# mainboard-raspi.net
KiCad netlist of a schematic drawn in EAGLE
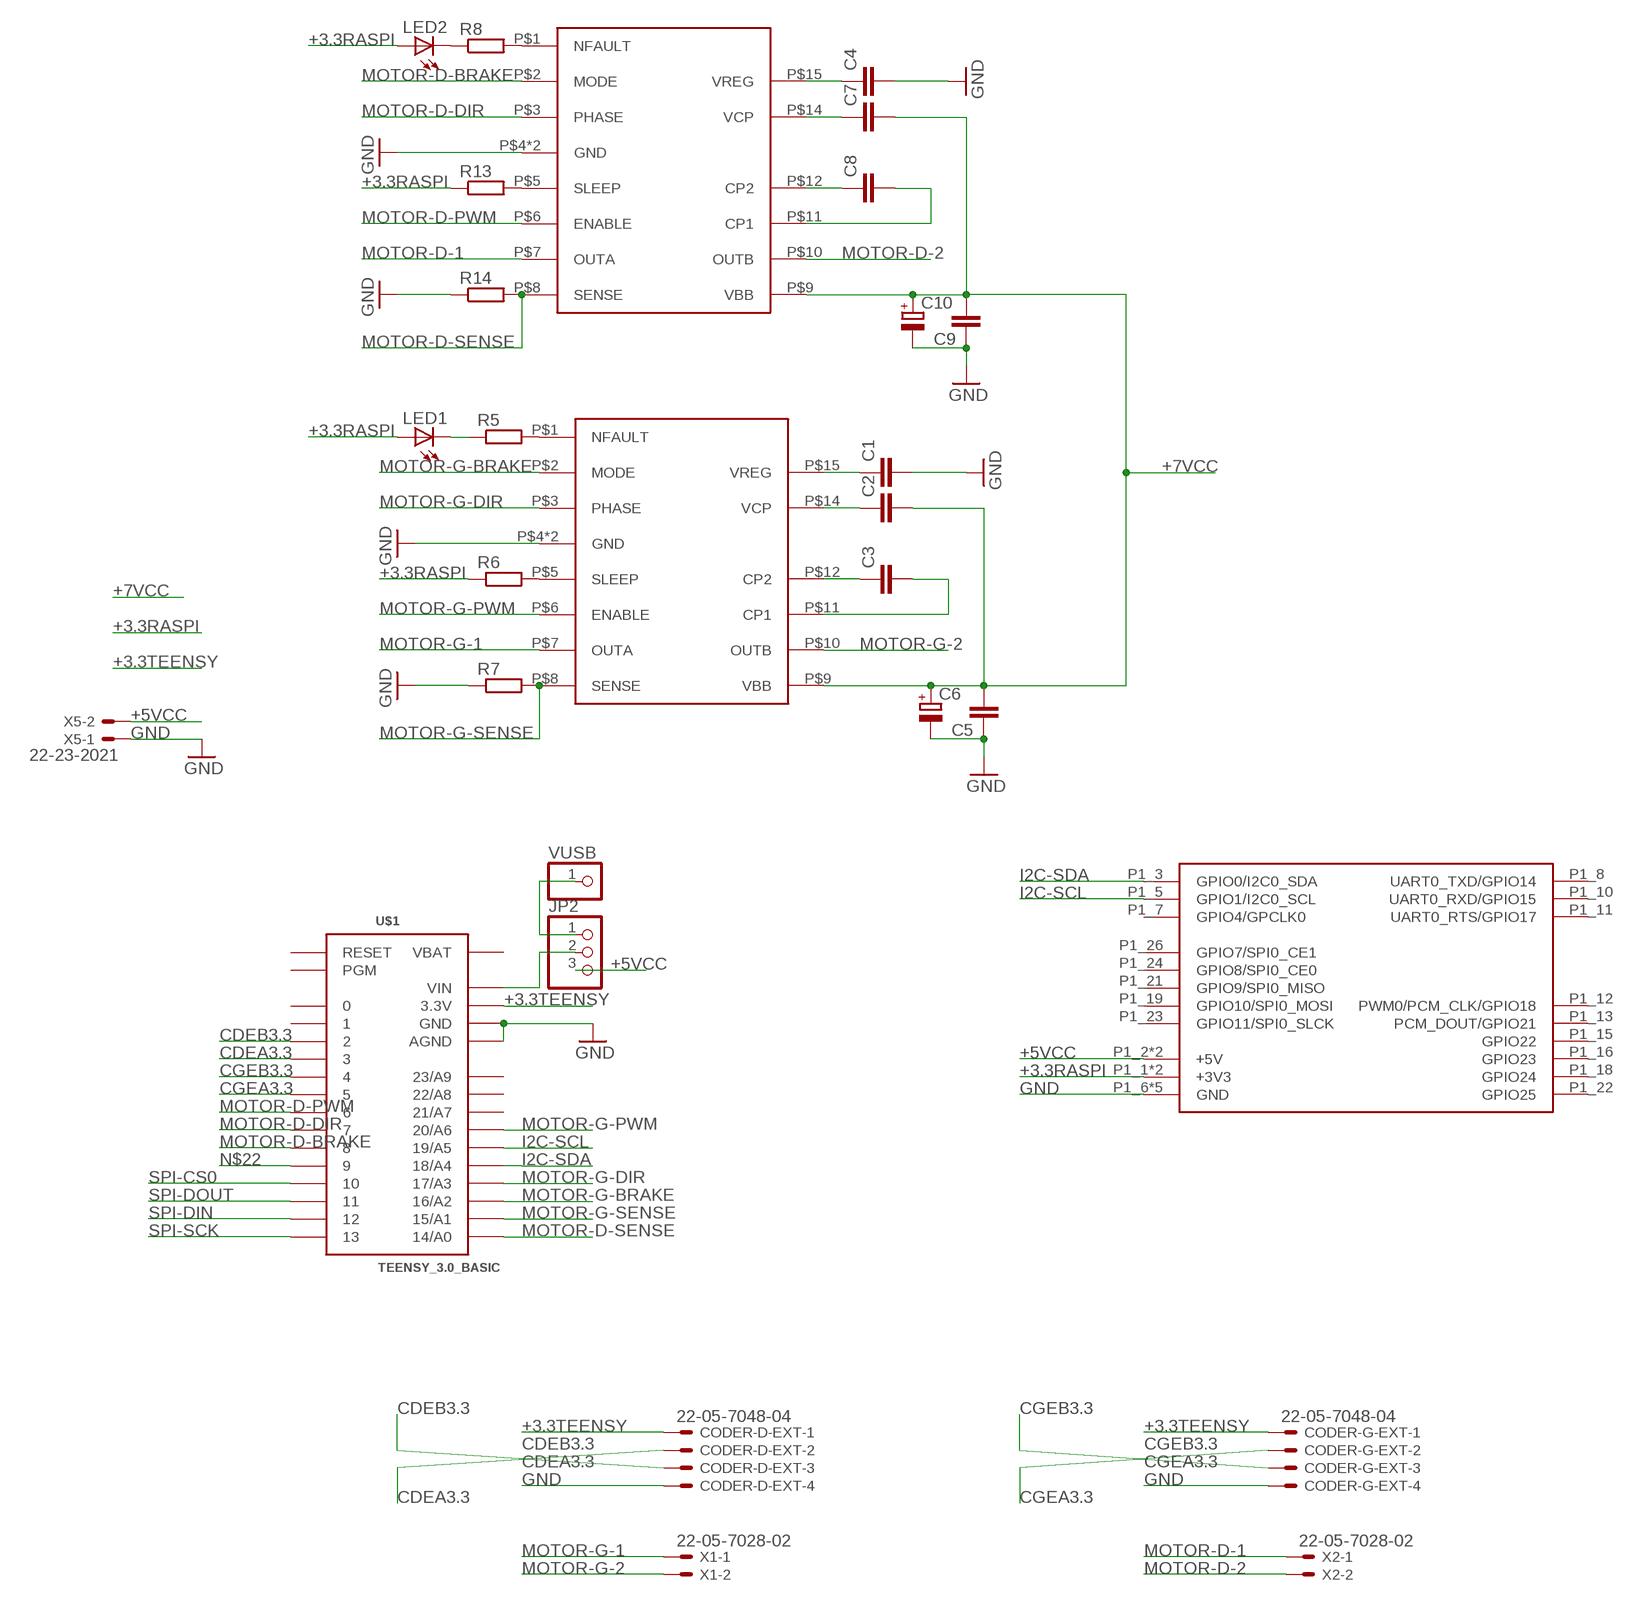
[diagram p0: schematic, sheet 1]

(export (version "E")
  (design (tool "Eeschema 10.0.6"))
  (components
    (comp (ref "C1")
      (value "C-EUC0805K")
      (footprint "eagle-import:C0805K")
      (libsource (lib "eagle-import") (part "C-EUC0805K"))
    )
    (comp (ref "C2")
      (value "C-EUC0805K")
      (footprint "eagle-import:C0805K")
      (libsource (lib "eagle-import") (part "C-EUC0805K"))
    )
    (comp (ref "C3")
      (value "C-EUC0805K")
      (footprint "eagle-import:C0805K")
      (libsource (lib "eagle-import") (part "C-EUC0805K"))
    )
    (comp (ref "C4")
      (value "C-EUC0805K")
      (footprint "eagle-import:C0805K")
      (libsource (lib "eagle-import") (part "C-EUC0805K"))
    )
    (comp (ref "C5")
      (value "C-EUC0805K")
      (footprint "eagle-import:C0805K")
      (libsource (lib "eagle-import") (part "C-EUC0805K"))
    )
    (comp (ref "C6")
      (value "CPOL-EUE3.5-8")
      (footprint "eagle-import:E3,5-8")
      (libsource (lib "eagle-import") (part "CPOL-EUE3.5-8"))
    )
    (comp (ref "C7")
      (value "C-EUC0805K")
      (footprint "eagle-import:C0805K")
      (libsource (lib "eagle-import") (part "C-EUC0805K"))
    )
    (comp (ref "C8")
      (value "C-EUC0805K")
      (footprint "eagle-import:C0805K")
      (libsource (lib "eagle-import") (part "C-EUC0805K"))
    )
    (comp (ref "C9")
      (value "C-EUC0805K")
      (footprint "eagle-import:C0805K")
      (libsource (lib "eagle-import") (part "C-EUC0805K"))
    )
    (comp (ref "C10")
      (value "CPOL-EUE3.5-8")
      (footprint "eagle-import:E3,5-8")
      (libsource (lib "eagle-import") (part "CPOL-EUE3.5-8"))
    )
    (comp (ref "CODER-D-EXT")
      (value "22-05-7048-04")
      (footprint "eagle-import:7395-04")
      (libsource (lib "eagle-import") (part "22-?-0405-7048"))
    )
    (comp (ref "CODER-G-EXT")
      (value "22-05-7048-04")
      (footprint "eagle-import:7395-04")
      (libsource (lib "eagle-import") (part "22-?-0405-7048"))
    )
    (comp (ref "JP2")
      (value "PINHD-1X3")
      (footprint "eagle-import:1X03")
      (libsource (lib "eagle-import") (part "PINHD-1X3"))
    )
    (comp (ref "LED1")
      (value "LED3MM")
      (footprint "eagle-import:LED3MM")
      (libsource (lib "eagle-import") (part "LED3MM"))
    )
    (comp (ref "LED2")
      (value "LED3MM")
      (footprint "eagle-import:LED3MM")
      (libsource (lib "eagle-import") (part "LED3MM"))
    )
    (comp (ref "R5")
      (value "R-EU_R0805W")
      (footprint "eagle-import:R0805W")
      (libsource (lib "eagle-import") (part "R-EU_R0805W"))
    )
    (comp (ref "R6")
      (value "R-EU_R0805W")
      (footprint "eagle-import:R0805W")
      (libsource (lib "eagle-import") (part "R-EU_R0805W"))
    )
    (comp (ref "R7")
      (value "R-EU_R0805W")
      (footprint "eagle-import:R0805W")
      (libsource (lib "eagle-import") (part "R-EU_R0805W"))
    )
    (comp (ref "R8")
      (value "R-EU_R0805W")
      (footprint "eagle-import:R0805W")
      (libsource (lib "eagle-import") (part "R-EU_R0805W"))
    )
    (comp (ref "R13")
      (value "R-EU_R0805W")
      (footprint "eagle-import:R0805W")
      (libsource (lib "eagle-import") (part "R-EU_R0805W"))
    )
    (comp (ref "R14")
      (value "R-EU_R0805W")
      (footprint "eagle-import:R0805W")
      (libsource (lib "eagle-import") (part "R-EU_R0805W"))
    )
    (comp (ref "U$1")
      (value "TEENSY_3.0_BASIC")
      (footprint "eagle-import:TEENSY_3.0_BASIC")
      (libsource (lib "eagle-import") (part "TEENSY_3.0_BASIC"))
    )
    (comp (ref "U$3")
      (value "A3950-DIL")
      (footprint "eagle-import:DIL16")
      (libsource (lib "eagle-import") (part "A3950-DIL"))
    )
    (comp (ref "U$4")
      (value "A3950-DIL")
      (footprint "eagle-import:DIL16")
      (libsource (lib "eagle-import") (part "A3950-DIL"))
    )
    (comp (ref "U$5")
      (value "RPI-B-V1SHIELD")
      (footprint "eagle-import:RPI-B-V1-SHIELD")
      (libsource (lib "eagle-import") (part "RPI-B-V1SHIELD"))
    )
    (comp (ref "VUSB")
      (value "PINHD-1X1")
      (footprint "eagle-import:1X01")
      (libsource (lib "eagle-import") (part "PINHD-1X1"))
    )
    (comp (ref "X1")
      (value "22-05-7028-02")
      (footprint "eagle-import:7395-02")
      (libsource (lib "eagle-import") (part "22-?-0205-7028"))
    )
    (comp (ref "X2")
      (value "22-05-7028-02")
      (footprint "eagle-import:7395-02")
      (libsource (lib "eagle-import") (part "22-?-0205-7028"))
    )
    (comp (ref "X5")
      (value "22-23-2021")
      (footprint "eagle-import:22-23-2021")
      (fields (field (name "MF") "MOLEX"))
      (libsource (lib "eagle-import") (part "22-23-2021"))
    )
  )
  (nets
    (net (code "1") (name "/+3.3RASPI") (class "Default")
      (node (ref "LED1") (pin "A") (pinfunction "A_A") (pintype "passive"))
      (node (ref "LED2") (pin "A") (pinfunction "A_A") (pintype "passive"))
      (node (ref "R13") (pin "1") (pinfunction "1_1") (pintype "passive"))
      (node (ref "R6") (pin "1") (pinfunction "1_1") (pintype "passive"))
      (node (ref "U$5") (pin "P1_1") (pinfunction "+3V3_P1_1") (pintype "power_in"))
      (node (ref "U$5") (pin "P1_17") (pinfunction "+3V3_P1_17") (pintype "power_in"))
    )
    (net (code "2") (name "/+3.3TEENSY") (class "Default")
      (node (ref "CODER-D-EXT") (pin "1") (pinfunction "S_1") (pintype "passive"))
      (node (ref "CODER-G-EXT") (pin "1") (pinfunction "S_1") (pintype "passive"))
      (node (ref "U$1") (pin "3.3V") (pinfunction "3.3V_3.3V") (pintype "power_in"))
      (node (ref "U$1") (pin "3.3V1") (pinfunction "3.3V_3.3V1") (pintype "power_in"))
    )
    (net (code "3") (name "/+5VCC") (class "Default")
      (node (ref "JP2") (pin "3") (pinfunction "3_3") (pintype "passive"))
      (node (ref "U$5") (pin "P1_2") (pinfunction "+5V_P1_2") (pintype "power_in"))
      (node (ref "U$5") (pin "P1_4") (pinfunction "+5V_P1_4") (pintype "power_in"))
      (node (ref "X5") (pin "2") (pinfunction "S_2") (pintype "passive"))
    )
    (net (code "4") (name "/+7VCC") (class "Default")
      (node (ref "C10") (pin "+") (pinfunction "+_+") (pintype "passive"))
      (node (ref "C2") (pin "2") (pinfunction "2_2") (pintype "passive"))
      (node (ref "C5") (pin "2") (pinfunction "2_2") (pintype "passive"))
      (node (ref "C6") (pin "+") (pinfunction "+_+") (pintype "passive"))
      (node (ref "C7") (pin "2") (pinfunction "2_2") (pintype "passive"))
      (node (ref "C9") (pin "2") (pinfunction "2_2") (pintype "passive"))
      (node (ref "U$3") (pin "P$9") (pinfunction "VBB_P$9") (pintype "bidirectional"))
      (node (ref "U$4") (pin "P$9") (pinfunction "VBB_P$9") (pintype "bidirectional"))
    )
    (net (code "5") (name "/CDEA3.3") (class "Default")
      (node (ref "CODER-D-EXT") (pin "2") (pinfunction "S_2") (pintype "passive"))
      (node (ref "U$1") (pin "3") (pinfunction "3_3") (pintype "bidirectional"))
    )
    (net (code "6") (name "/CDEB3.3") (class "Default")
      (node (ref "CODER-D-EXT") (pin "3") (pinfunction "S_3") (pintype "passive"))
      (node (ref "U$1") (pin "2") (pinfunction "2_2") (pintype "bidirectional"))
    )
    (net (code "7") (name "/CGEA3.3") (class "Default")
      (node (ref "CODER-G-EXT") (pin "2") (pinfunction "S_2") (pintype "passive"))
      (node (ref "U$1") (pin "5") (pinfunction "5_5") (pintype "bidirectional"))
    )
    (net (code "8") (name "/CGEB3.3") (class "Default")
      (node (ref "CODER-G-EXT") (pin "3") (pinfunction "S_3") (pintype "passive"))
      (node (ref "U$1") (pin "4") (pinfunction "4_4") (pintype "bidirectional"))
    )
    (net (code "9") (name "/I2C-SCL") (class "Default")
      (node (ref "U$1") (pin "19/A5") (pinfunction "19/A5_19/A5") (pintype "bidirectional"))
      (node (ref "U$5") (pin "P1_5") (pinfunction "GPIO1/I2C0_SCL_P1_5") (pintype "bidirectional"))
    )
    (net (code "10") (name "/I2C-SDA") (class "Default")
      (node (ref "U$1") (pin "18/A4") (pinfunction "18/A4_18/A4") (pintype "bidirectional"))
      (node (ref "U$5") (pin "P1_3") (pinfunction "GPIO0/I2C0_SDA_P1_3") (pintype "bidirectional"))
    )
    (net (code "11") (name "/MOTOR-D-1") (class "Default")
      (node (ref "U$4") (pin "P$7") (pinfunction "OUTA_P$7") (pintype "bidirectional"))
      (node (ref "X2") (pin "1") (pinfunction "S_1") (pintype "passive"))
    )
    (net (code "12") (name "/MOTOR-D-2") (class "Default")
      (node (ref "U$4") (pin "P$10") (pinfunction "OUTB_P$10") (pintype "bidirectional"))
      (node (ref "X2") (pin "2") (pinfunction "S_2") (pintype "passive"))
    )
    (net (code "13") (name "/MOTOR-D-BRAKE") (class "Default")
      (node (ref "U$1") (pin "8") (pinfunction "8_8") (pintype "bidirectional"))
      (node (ref "U$4") (pin "P$2") (pinfunction "MODE_P$2") (pintype "bidirectional"))
    )
    (net (code "14") (name "/MOTOR-D-DIR") (class "Default")
      (node (ref "U$1") (pin "7") (pinfunction "7_7") (pintype "bidirectional"))
      (node (ref "U$4") (pin "P$3") (pinfunction "PHASE_P$3") (pintype "bidirectional"))
    )
    (net (code "15") (name "/MOTOR-D-PWM") (class "Default")
      (node (ref "U$1") (pin "6") (pinfunction "6_6") (pintype "bidirectional"))
      (node (ref "U$4") (pin "P$6") (pinfunction "ENABLE_P$6") (pintype "bidirectional"))
    )
    (net (code "16") (name "/MOTOR-D-SENSE") (class "Default")
      (node (ref "R14") (pin "2") (pinfunction "2_2") (pintype "passive"))
      (node (ref "U$1") (pin "14/A0") (pinfunction "14/A0_14/A0") (pintype "bidirectional"))
      (node (ref "U$4") (pin "P$8") (pinfunction "SENSE_P$8") (pintype "bidirectional"))
    )
    (net (code "17") (name "/MOTOR-G-1") (class "Default")
      (node (ref "U$3") (pin "P$7") (pinfunction "OUTA_P$7") (pintype "bidirectional"))
      (node (ref "X1") (pin "1") (pinfunction "S_1") (pintype "passive"))
    )
    (net (code "18") (name "/MOTOR-G-2") (class "Default")
      (node (ref "U$3") (pin "P$10") (pinfunction "OUTB_P$10") (pintype "bidirectional"))
      (node (ref "X1") (pin "2") (pinfunction "S_2") (pintype "passive"))
    )
    (net (code "19") (name "/MOTOR-G-BRAKE") (class "Default")
      (node (ref "U$1") (pin "16/A2") (pinfunction "16/A2_16/A2") (pintype "bidirectional"))
      (node (ref "U$3") (pin "P$2") (pinfunction "MODE_P$2") (pintype "bidirectional"))
    )
    (net (code "20") (name "/MOTOR-G-DIR") (class "Default")
      (node (ref "U$1") (pin "17/A3") (pinfunction "17/A3_17/A3") (pintype "bidirectional"))
      (node (ref "U$3") (pin "P$3") (pinfunction "PHASE_P$3") (pintype "bidirectional"))
    )
    (net (code "21") (name "/MOTOR-G-PWM") (class "Default")
      (node (ref "U$1") (pin "20/A6") (pinfunction "20/A6_20/A6") (pintype "bidirectional"))
      (node (ref "U$3") (pin "P$6") (pinfunction "ENABLE_P$6") (pintype "bidirectional"))
    )
    (net (code "22") (name "/MOTOR-G-SENSE") (class "Default")
      (node (ref "R7") (pin "2") (pinfunction "2_2") (pintype "passive"))
      (node (ref "U$1") (pin "15/A1") (pinfunction "15/A1_15/A1") (pintype "bidirectional"))
      (node (ref "U$3") (pin "P$8") (pinfunction "SENSE_P$8") (pintype "bidirectional"))
    )
    (net (code "23") (name "/N$22") (class "Default")
      (node (ref "U$1") (pin "9") (pinfunction "9_9") (pintype "bidirectional"))
    )
    (net (code "24") (name "/SPI-CS0") (class "Default")
      (node (ref "U$1") (pin "10") (pinfunction "10_10") (pintype "bidirectional"))
    )
    (net (code "25") (name "/SPI-DIN") (class "Default")
      (node (ref "U$1") (pin "12") (pinfunction "12_12") (pintype "bidirectional"))
    )
    (net (code "26") (name "/SPI-DOUT") (class "Default")
      (node (ref "U$1") (pin "11") (pinfunction "11_11") (pintype "bidirectional"))
    )
    (net (code "27") (name "/SPI-SCK") (class "Default")
      (node (ref "U$1") (pin "13") (pinfunction "13_13") (pintype "bidirectional"))
    )
    (net (code "28") (name "/VBAT") (class "Default")
      (node (ref "U$1") (pin "VBAT") (pinfunction "VBAT_VBAT") (pintype "power_in"))
    )
    (net (code "29") (name "GND") (class "Default")
      (node (ref "C1") (pin "2") (pinfunction "2_2") (pintype "passive"))
      (node (ref "C10") (pin "-") (pinfunction "-_-") (pintype "passive"))
      (node (ref "C4") (pin "2") (pinfunction "2_2") (pintype "passive"))
      (node (ref "C5") (pin "1") (pinfunction "1_1") (pintype "passive"))
      (node (ref "C6") (pin "-") (pinfunction "-_-") (pintype "passive"))
      (node (ref "C9") (pin "1") (pinfunction "1_1") (pintype "passive"))
      (node (ref "CODER-D-EXT") (pin "4") (pinfunction "S_4") (pintype "passive"))
      (node (ref "CODER-G-EXT") (pin "4") (pinfunction "S_4") (pintype "passive"))
      (node (ref "R14") (pin "1") (pinfunction "1_1") (pintype "passive"))
      (node (ref "R7") (pin "1") (pinfunction "1_1") (pintype "passive"))
      (node (ref "U$1") (pin "AGND") (pinfunction "AGND_AGND") (pintype "power_in"))
      (node (ref "U$1") (pin "GND") (pinfunction "GND_GND") (pintype "power_in"))
      (node (ref "U$1") (pin "GND1") (pinfunction "GND_GND1") (pintype "power_in"))
      (node (ref "U$3") (pin "P$13") (pinfunction "GND_P$13") (pintype "bidirectional"))
      (node (ref "U$3") (pin "P$4") (pinfunction "GND_P$4") (pintype "bidirectional"))
      (node (ref "U$4") (pin "P$13") (pinfunction "GND_P$13") (pintype "bidirectional"))
      (node (ref "U$4") (pin "P$4") (pinfunction "GND_P$4") (pintype "bidirectional"))
      (node (ref "U$5") (pin "P1_14") (pinfunction "GND_P1_14") (pintype "power_in"))
      (node (ref "U$5") (pin "P1_20") (pinfunction "GND_P1_20") (pintype "power_in"))
      (node (ref "U$5") (pin "P1_25") (pinfunction "GND_P1_25") (pintype "power_in"))
      (node (ref "U$5") (pin "P1_6") (pinfunction "GND_P1_6") (pintype "power_in"))
      (node (ref "U$5") (pin "P1_9") (pinfunction "GND_P1_9") (pintype "power_in"))
      (node (ref "X5") (pin "1") (pinfunction "S_1") (pintype "passive"))
    )
    (net (code "30") (name "Net-(JP2-Pad1)") (class "Default")
      (node (ref "JP2") (pin "1") (pinfunction "1_1") (pintype "passive"))
      (node (ref "VUSB") (pin "1") (pinfunction "1_1") (pintype "passive"))
    )
    (net (code "31") (name "Net-(JP2-Pad2)") (class "Default")
      (node (ref "JP2") (pin "2") (pinfunction "2_2") (pintype "passive"))
      (node (ref "U$1") (pin "VIN") (pinfunction "VIN_VIN") (pintype "power_in"))
    )
    (net (code "32") (name "Net-(LED1-C)") (class "Default")
      (node (ref "LED1") (pin "K") (pinfunction "C_K") (pintype "passive"))
      (node (ref "R5") (pin "1") (pinfunction "1_1") (pintype "passive"))
    )
    (net (code "33") (name "Net-(LED2-C)") (class "Default")
      (node (ref "LED2") (pin "K") (pinfunction "C_K") (pintype "passive"))
      (node (ref "R8") (pin "1") (pinfunction "1_1") (pintype "passive"))
    )
    (net (code "34") (name "Net-(U$3-CP1)") (class "Default")
      (node (ref "C3") (pin "2") (pinfunction "2_2") (pintype "passive"))
      (node (ref "U$3") (pin "P$11") (pinfunction "CP1_P$11") (pintype "bidirectional"))
    )
    (net (code "35") (name "Net-(U$3-CP2)") (class "Default")
      (node (ref "C3") (pin "1") (pinfunction "1_1") (pintype "passive"))
      (node (ref "U$3") (pin "P$12") (pinfunction "CP2_P$12") (pintype "bidirectional"))
    )
    (net (code "36") (name "Net-(U$3-NFAULT)") (class "Default")
      (node (ref "R5") (pin "2") (pinfunction "2_2") (pintype "passive"))
      (node (ref "U$3") (pin "P$1") (pinfunction "NFAULT_P$1") (pintype "bidirectional"))
    )
    (net (code "37") (name "Net-(U$3-SLEEP)") (class "Default")
      (node (ref "R6") (pin "2") (pinfunction "2_2") (pintype "passive"))
      (node (ref "U$3") (pin "P$5") (pinfunction "SLEEP_P$5") (pintype "bidirectional"))
    )
    (net (code "38") (name "Net-(U$3-VCP)") (class "Default")
      (node (ref "C2") (pin "1") (pinfunction "1_1") (pintype "passive"))
      (node (ref "U$3") (pin "P$14") (pinfunction "VCP_P$14") (pintype "bidirectional"))
    )
    (net (code "39") (name "Net-(U$3-VREG)") (class "Default")
      (node (ref "C1") (pin "1") (pinfunction "1_1") (pintype "passive"))
      (node (ref "U$3") (pin "P$15") (pinfunction "VREG_P$15") (pintype "bidirectional"))
    )
    (net (code "40") (name "Net-(U$4-CP1)") (class "Default")
      (node (ref "C8") (pin "2") (pinfunction "2_2") (pintype "passive"))
      (node (ref "U$4") (pin "P$11") (pinfunction "CP1_P$11") (pintype "bidirectional"))
    )
    (net (code "41") (name "Net-(U$4-CP2)") (class "Default")
      (node (ref "C8") (pin "1") (pinfunction "1_1") (pintype "passive"))
      (node (ref "U$4") (pin "P$12") (pinfunction "CP2_P$12") (pintype "bidirectional"))
    )
    (net (code "42") (name "Net-(U$4-NFAULT)") (class "Default")
      (node (ref "R8") (pin "2") (pinfunction "2_2") (pintype "passive"))
      (node (ref "U$4") (pin "P$1") (pinfunction "NFAULT_P$1") (pintype "bidirectional"))
    )
    (net (code "43") (name "Net-(U$4-SLEEP)") (class "Default")
      (node (ref "R13") (pin "2") (pinfunction "2_2") (pintype "passive"))
      (node (ref "U$4") (pin "P$5") (pinfunction "SLEEP_P$5") (pintype "bidirectional"))
    )
    (net (code "44") (name "Net-(U$4-VCP)") (class "Default")
      (node (ref "C7") (pin "1") (pinfunction "1_1") (pintype "passive"))
      (node (ref "U$4") (pin "P$14") (pinfunction "VCP_P$14") (pintype "bidirectional"))
    )
    (net (code "45") (name "Net-(U$4-VREG)") (class "Default")
      (node (ref "C4") (pin "1") (pinfunction "1_1") (pintype "passive"))
      (node (ref "U$4") (pin "P$15") (pinfunction "VREG_P$15") (pintype "bidirectional"))
    )
    (net (code "46") (name "unconnected-(U$1-Pad0)") (class "Default")
      (node (ref "U$1") (pin "0") (pinfunction "0_0") (pintype "bidirectional"))
    )
    (net (code "47") (name "unconnected-(U$1-Pad1)") (class "Default")
      (node (ref "U$1") (pin "1") (pinfunction "1_1") (pintype "bidirectional"))
    )
    (net (code "48") (name "unconnected-(U$1-Pad21{slash}A7)") (class "Default")
      (node (ref "U$1") (pin "21/A7") (pinfunction "21/A7_21/A7") (pintype "bidirectional"))
    )
    (net (code "49") (name "unconnected-(U$1-Pad22{slash}A8)") (class "Default")
      (node (ref "U$1") (pin "22/A8") (pinfunction "22/A8_22/A8") (pintype "bidirectional"))
    )
    (net (code "50") (name "unconnected-(U$1-Pad23{slash}A9)") (class "Default")
      (node (ref "U$1") (pin "23/A9") (pinfunction "23/A9_23/A9") (pintype "bidirectional"))
    )
    (net (code "51") (name "unconnected-(U$1-PadPGM)") (class "Default")
      (node (ref "U$1") (pin "PGM") (pinfunction "PGM_PGM") (pintype "bidirectional"))
    )
    (net (code "52") (name "unconnected-(U$1-PadRESET)") (class "Default")
      (node (ref "U$1") (pin "RESET") (pinfunction "RESET_RESET") (pintype "bidirectional"))
    )
    (net (code "53") (name "unconnected-(U$5-GPIO4{slash}GPCLK0-PadP1_7)") (class "Default")
      (node (ref "U$5") (pin "P1_7") (pinfunction "GPIO4/GPCLK0_P1_7") (pintype "bidirectional"))
    )
    (net (code "54") (name "unconnected-(U$5-GPIO7{slash}SPI0_CE1-PadP1_26)") (class "Default")
      (node (ref "U$5") (pin "P1_26") (pinfunction "GPIO7/SPI0_CE1_P1_26") (pintype "bidirectional"))
    )
    (net (code "55") (name "unconnected-(U$5-GPIO8{slash}SPI0_CE0-PadP1_24)") (class "Default")
      (node (ref "U$5") (pin "P1_24") (pinfunction "GPIO8/SPI0_CE0_P1_24") (pintype "bidirectional"))
    )
    (net (code "56") (name "unconnected-(U$5-GPIO9{slash}SPI0_MISO-PadP1_21)") (class "Default")
      (node (ref "U$5") (pin "P1_21") (pinfunction "GPIO9/SPI0_MISO_P1_21") (pintype "bidirectional"))
    )
    (net (code "57") (name "unconnected-(U$5-GPIO10{slash}SPI0_MOSI-PadP1_19)") (class "Default")
      (node (ref "U$5") (pin "P1_19") (pinfunction "GPIO10/SPI0_MOSI_P1_19") (pintype "bidirectional"))
    )
    (net (code "58") (name "unconnected-(U$5-GPIO11{slash}SPI0_SLCK-PadP1_23)") (class "Default")
      (node (ref "U$5") (pin "P1_23") (pinfunction "GPIO11/SPI0_SLCK_P1_23") (pintype "bidirectional"))
    )
    (net (code "59") (name "unconnected-(U$5-GPIO22-PadP1_15)") (class "Default")
      (node (ref "U$5") (pin "P1_15") (pinfunction "GPIO22_P1_15") (pintype "bidirectional"))
    )
    (net (code "60") (name "unconnected-(U$5-GPIO23-PadP1_16)") (class "Default")
      (node (ref "U$5") (pin "P1_16") (pinfunction "GPIO23_P1_16") (pintype "bidirectional"))
    )
    (net (code "61") (name "unconnected-(U$5-GPIO24-PadP1_18)") (class "Default")
      (node (ref "U$5") (pin "P1_18") (pinfunction "GPIO24_P1_18") (pintype "bidirectional"))
    )
    (net (code "62") (name "unconnected-(U$5-GPIO25-PadP1_22)") (class "Default")
      (node (ref "U$5") (pin "P1_22") (pinfunction "GPIO25_P1_22") (pintype "bidirectional"))
    )
    (net (code "63") (name "unconnected-(U$5-PCM_DOUT{slash}GPIO21-PadP1_13)") (class "Default")
      (node (ref "U$5") (pin "P1_13") (pinfunction "PCM_DOUT/GPIO21_P1_13") (pintype "bidirectional"))
    )
    (net (code "64") (name "unconnected-(U$5-PWM0{slash}PCM_CLK{slash}GPIO18-PadP1_12)") (class "Default")
      (node (ref "U$5") (pin "P1_12") (pinfunction "PWM0/PCM_CLK/GPIO18_P1_12") (pintype "bidirectional"))
    )
    (net (code "65") (name "unconnected-(U$5-UART0_RTS{slash}GPIO17-PadP1_11)") (class "Default")
      (node (ref "U$5") (pin "P1_11") (pinfunction "UART0_RTS/GPIO17_P1_11") (pintype "bidirectional"))
    )
    (net (code "66") (name "unconnected-(U$5-UART0_RXD{slash}GPIO15-PadP1_10)") (class "Default")
      (node (ref "U$5") (pin "P1_10") (pinfunction "UART0_RXD/GPIO15_P1_10") (pintype "bidirectional"))
    )
    (net (code "67") (name "unconnected-(U$5-UART0_TXD{slash}GPIO14-PadP1_8)") (class "Default")
      (node (ref "U$5") (pin "P1_8") (pinfunction "UART0_TXD/GPIO14_P1_8") (pintype "bidirectional"))
    )
  )
)
